# NinjaPCB_ver2_1.net
KiCad netlist of a schematic drawn in EAGLE
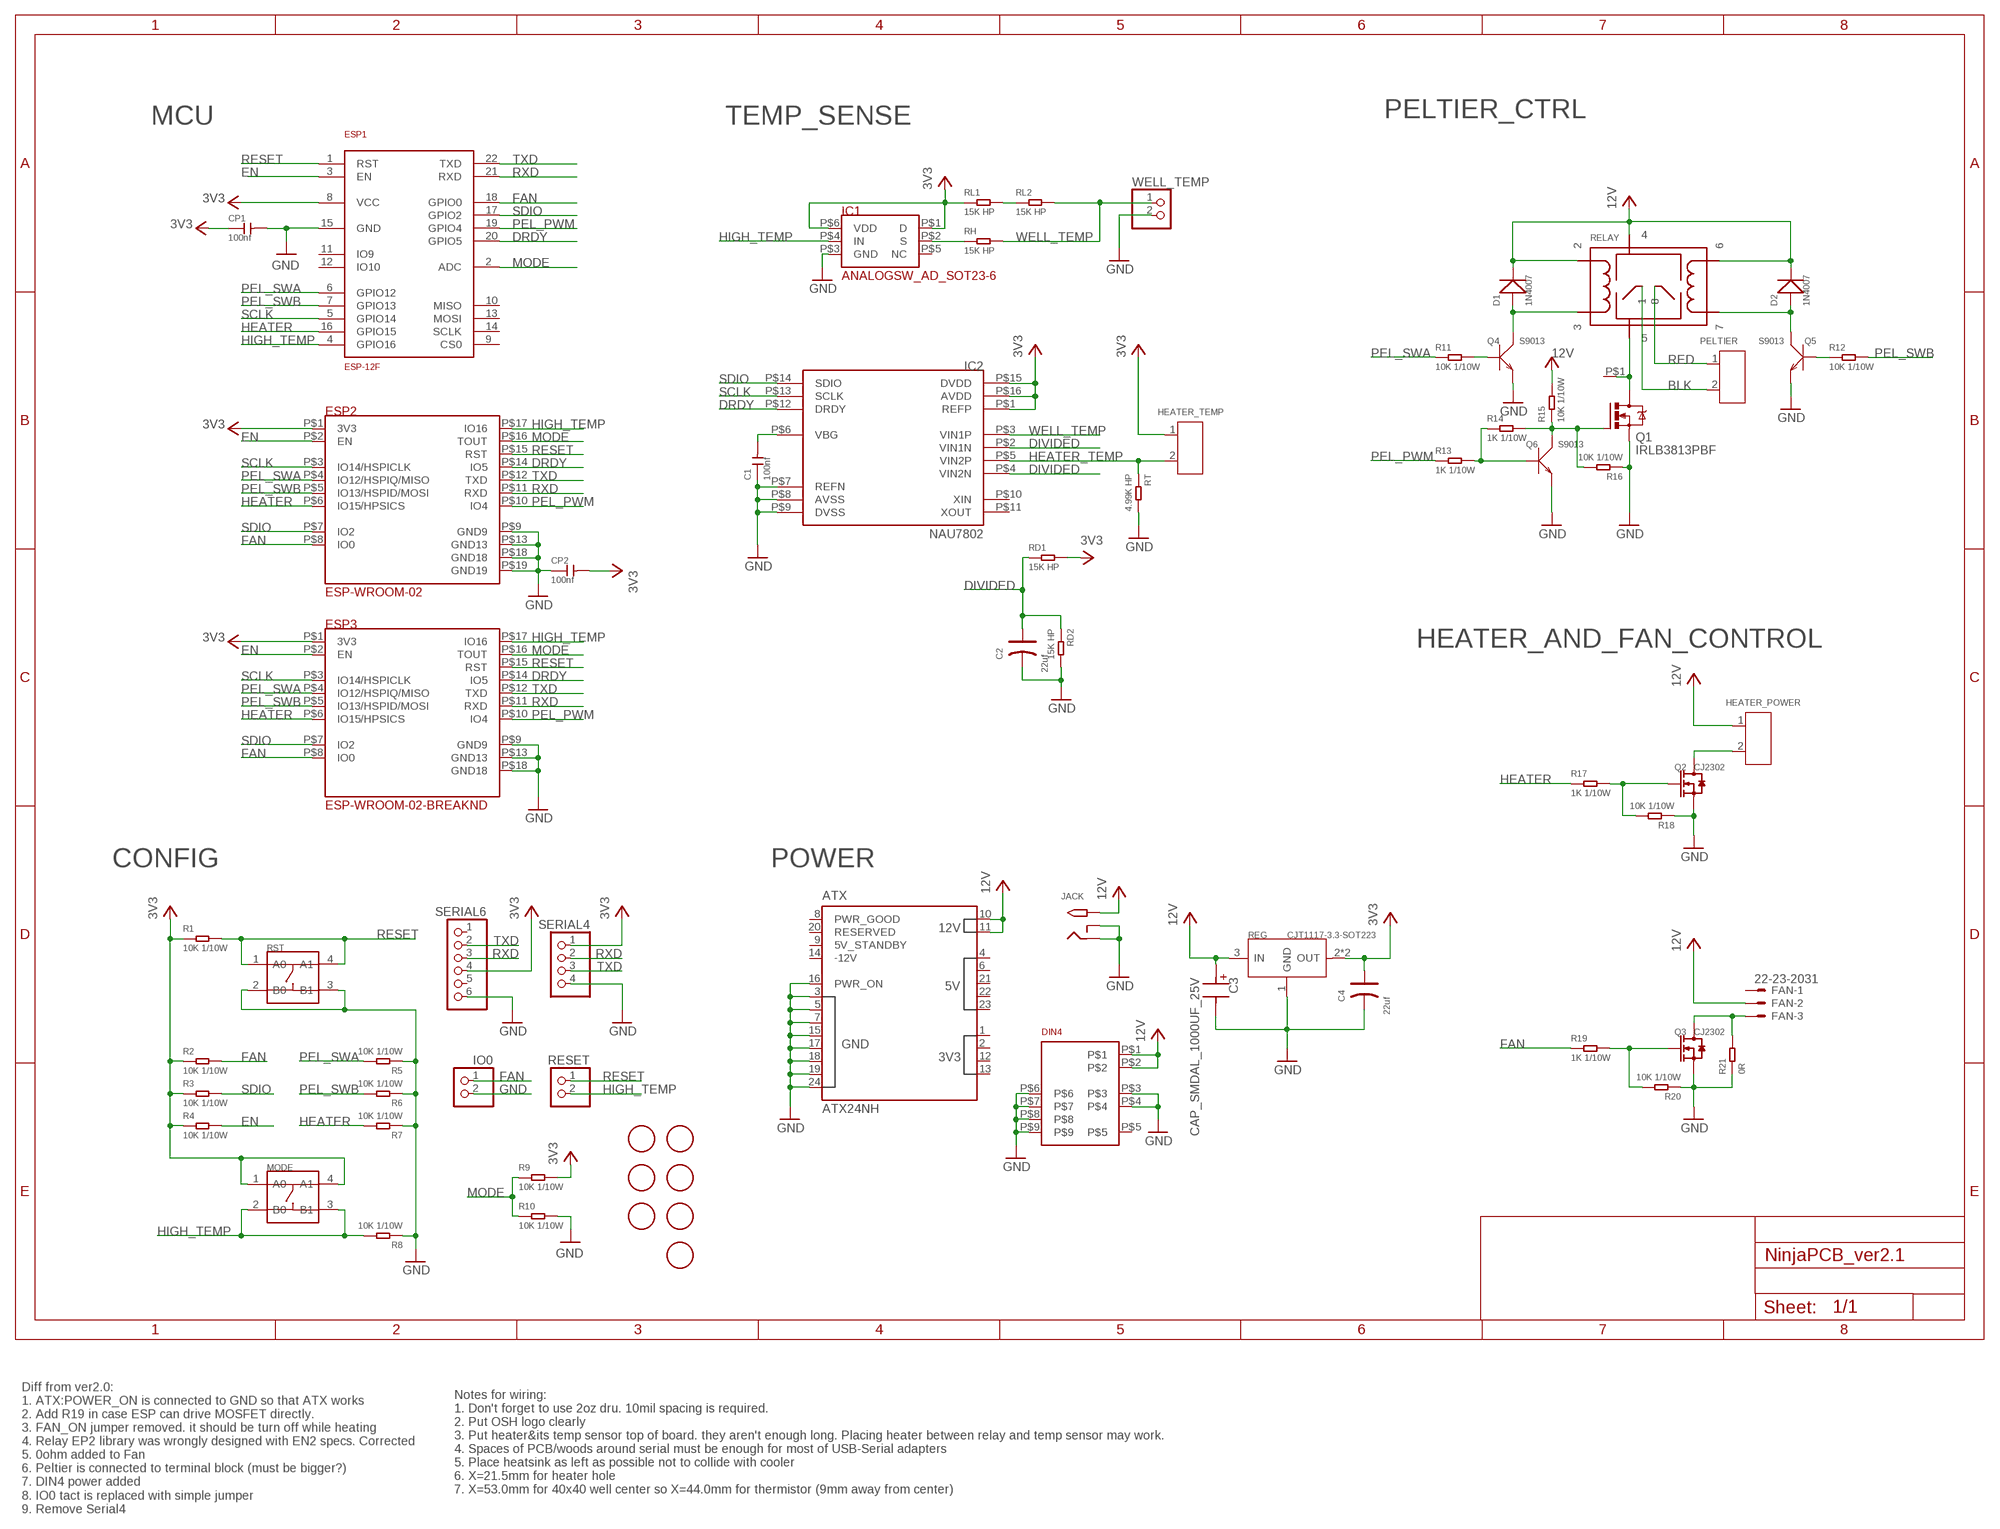
[diagram p0: schematic, sheet 1]

(export (version "E")
  (design (tool "Eeschema 10.0.6"))
  (components
    (comp (ref "ATX")
      (value "ATX24NH")
      (footprint "eagle-import:ATX24")
      (libsource (lib "eagle-import") (part "ATX24NH"))
    )
    (comp (ref "C1")
      (value "100nf")
      (footprint "eagle-import:C0603")
      (fields (field (name "MPN") "CC0603KRX7R9BB104"))
      (libsource (lib "eagle-import") (part "CERAMIC-100NF-50V-10%-X7R(0603)"))
    )
    (comp (ref "C2")
      (value "22uf")
      (footprint "eagle-import:AVX-B")
      (fields (field (name "MPN") "TAJB226*016#NJ"))
      (libsource (lib "eagle-import") (part "TANTALUM-SMD-22UF-16V(AVX-B)"))
    )
    (comp (ref "C3")
      (value "CAP_SMDAL_1000UF_25V")
      (footprint "eagle-import:CAP_SMD_AL_D125")
      (libsource (lib "eagle-import") (part "CAP_SMDAL_1000UF_25V"))
    )
    (comp (ref "C4")
      (value "22uf")
      (footprint "eagle-import:AVX-B")
      (fields (field (name "MPN") "TAJB226*016#NJ"))
      (libsource (lib "eagle-import") (part "TANTALUM-SMD-22UF-16V(AVX-B)"))
    )
    (comp (ref "CP1")
      (value "100nf")
      (footprint "eagle-import:C0603")
      (fields (field (name "MPN") "CC0603KRX7R9BB104"))
      (libsource (lib "eagle-import") (part "CERAMIC-100NF-50V-10%-X7R(0603)"))
    )
    (comp (ref "CP2")
      (value "100nf")
      (footprint "eagle-import:C0603")
      (fields (field (name "MPN") "CC0603KRX7R9BB104"))
      (libsource (lib "eagle-import") (part "CERAMIC-100NF-50V-10%-X7R(0603)"))
    )
    (comp (ref "D1")
      (value "1N4007")
      (footprint "eagle-import:DO-214AC")
      (libsource (lib "eagle-import") (part "DIODE-GEN-PURPOSE-1KV-1A(DO-214AC)"))
    )
    (comp (ref "D2")
      (value "1N4007")
      (footprint "eagle-import:DO-214AC")
      (libsource (lib "eagle-import") (part "DIODE-GEN-PURPOSE-1KV-1A(DO-214AC)"))
    )
    (comp (ref "DIN4")
      (value "DIN4")
      (footprint "eagle-import:DIN4")
      (libsource (lib "eagle-import") (part "DIN4"))
    )
    (comp (ref "ESP1")
      (value "ESP-12F")
      (footprint "eagle-import:ESP-12F")
      (libsource (lib "eagle-import") (part "ESP-12F"))
    )
    (comp (ref "ESP2")
      (value "ESP-WROOM-02")
      (footprint "eagle-import:ESP-WROOM-02")
      (libsource (lib "eagle-import") (part "ESP-WROOM-02"))
    )
    (comp (ref "ESP3")
      (value "ESP-WROOM-02-BREAKND")
      (footprint "eagle-import:ESP-WROOM-02-BREAK-NODETAIL")
      (libsource (lib "eagle-import") (part "ESP-WROOM-02-BREAKND"))
    )
    (comp (ref "FAN")
      (value "22-23-2031")
      (footprint "eagle-import:22-23-2031")
      (fields (field (name "MF") "MOLEX"))
      (libsource (lib "eagle-import") (part "22-23-2031"))
    )
    (comp (ref "HEATER_POWER")
      (value "SCREW-TERMINAL-GREEN(2P-3.5)")
      (footprint "eagle-import:H2-3.5-7.0X7.0MM")
      (libsource (lib "eagle-import") (part "SCREW-TERMINAL-GREEN(2P-3.5)"))
    )
    (comp (ref "HEATER_TEMP")
      (value "SCREW-TERMINAL-GREEN(2P-3.5)")
      (footprint "eagle-import:H2-3.5-7.0X7.0MM")
      (libsource (lib "eagle-import") (part "SCREW-TERMINAL-GREEN(2P-3.5)"))
    )
    (comp (ref "HEATSINK")
      (value "HEAT111PB015")
      (footprint "eagle-import:HEAT11PB015")
      (libsource (lib "eagle-import") (part "HEAT111PB015"))
    )
    (comp (ref "IC1")
      (value "ANALOGSW_AD_SOT23-6")
      (footprint "eagle-import:SOT-23-6")
      (libsource (lib "eagle-import") (part "ANALOGSW_AD_SOT23-6"))
    )
    (comp (ref "IC2")
      (value "NAU7802")
      (footprint "eagle-import:SOP-16")
      (libsource (lib "eagle-import") (part "NAU7802"))
    )
    (comp (ref "IO0")
      (value "PINHD-1X2")
      (footprint "eagle-import:1X02")
      (libsource (lib "eagle-import") (part "PINHD-1X2"))
    )
    (comp (ref "JACK")
      (value "2.1MMJACKTHM-NOOUT")
      (footprint "eagle-import:PJ-102A-NOOUT")
      (libsource (lib "eagle-import") (part "2.1MMJACKTHM-NOOUT"))
    )
    (comp (ref "MODE")
      (value "DIP-SWITCH-TACTILE-SPST-NO/TS-1109(4P-D6.0MM)'TS-1109'")
      (footprint "eagle-import:SW4-6.0X6.0X5.0MM")
      (libsource (lib "eagle-import") (part "DIP-SWITCH-TACTILE-SPST-NO/TS-1109(4P-D6.0MM)'TS-1109'"))
    )
    (comp (ref "PELTIER")
      (value "SCREW-TERMINAL-GREEN(2P-3.5)")
      (footprint "eagle-import:H2-3.5-7.0X7.0MM")
      (libsource (lib "eagle-import") (part "SCREW-TERMINAL-GREEN(2P-3.5)"))
    )
    (comp (ref "Q1")
      (value "IRLB3813PBF")
      (footprint "eagle-import:TO220BV")
      (libsource (lib "eagle-import") (part "IRF520"))
    )
    (comp (ref "Q2")
      (value "CJ2302")
      (footprint "eagle-import:SOT-23")
      (libsource (lib "eagle-import") (part "SMD-MOSFET-N-CH-20V-2.1A-CJ2302(SOT-23)"))
    )
    (comp (ref "Q3")
      (value "CJ2302")
      (footprint "eagle-import:SOT-23")
      (libsource (lib "eagle-import") (part "SMD-MOSFET-N-CH-20V-2.1A-CJ2302(SOT-23)"))
    )
    (comp (ref "Q4")
      (value "S9013")
      (footprint "eagle-import:SOT-23")
      (libsource (lib "eagle-import") (part "SMD-TRANSISTORS-NPN-25V-500MA-S9013(SOT-23)"))
    )
    (comp (ref "Q5")
      (value "S9013")
      (footprint "eagle-import:SOT-23")
      (libsource (lib "eagle-import") (part "SMD-TRANSISTORS-NPN-25V-500MA-S9013(SOT-23)"))
    )
    (comp (ref "Q6")
      (value "S9013")
      (footprint "eagle-import:SOT-23")
      (libsource (lib "eagle-import") (part "SMD-TRANSISTORS-NPN-25V-500MA-S9013(SOT-23)"))
    )
    (comp (ref "R1")
      (value "10K 1/10W")
      (footprint "eagle-import:R0603")
      (fields (field (name "MPN") "RC0603JR-0710KL"))
      (libsource (lib "eagle-import") (part "SMD-RES-10K-5%-1/10W(0603)"))
    )
    (comp (ref "R2")
      (value "10K 1/10W")
      (footprint "eagle-import:R0603")
      (fields (field (name "MPN") "RC0603JR-0710KL"))
      (libsource (lib "eagle-import") (part "SMD-RES-10K-5%-1/10W(0603)"))
    )
    (comp (ref "R3")
      (value "10K 1/10W")
      (footprint "eagle-import:R0603")
      (fields (field (name "MPN") "RC0603JR-0710KL"))
      (libsource (lib "eagle-import") (part "SMD-RES-10K-5%-1/10W(0603)"))
    )
    (comp (ref "R4")
      (value "10K 1/10W")
      (footprint "eagle-import:R0603")
      (fields (field (name "MPN") "RC0603JR-0710KL"))
      (libsource (lib "eagle-import") (part "SMD-RES-10K-5%-1/10W(0603)"))
    )
    (comp (ref "R5")
      (value "10K 1/10W")
      (footprint "eagle-import:R0603")
      (fields (field (name "MPN") "RC0603JR-0710KL"))
      (libsource (lib "eagle-import") (part "SMD-RES-10K-5%-1/10W(0603)"))
    )
    (comp (ref "R6")
      (value "10K 1/10W")
      (footprint "eagle-import:R0603")
      (fields (field (name "MPN") "RC0603JR-0710KL"))
      (libsource (lib "eagle-import") (part "SMD-RES-10K-5%-1/10W(0603)"))
    )
    (comp (ref "R7")
      (value "10K 1/10W")
      (footprint "eagle-import:R0603")
      (fields (field (name "MPN") "RC0603JR-0710KL"))
      (libsource (lib "eagle-import") (part "SMD-RES-10K-5%-1/10W(0603)"))
    )
    (comp (ref "R8")
      (value "10K 1/10W")
      (footprint "eagle-import:R0603")
      (fields (field (name "MPN") "RC0603JR-0710KL"))
      (libsource (lib "eagle-import") (part "SMD-RES-10K-5%-1/10W(0603)"))
    )
    (comp (ref "R9")
      (value "10K 1/10W")
      (footprint "eagle-import:R0603")
      (fields (field (name "MPN") "RC0603JR-0710KL"))
      (libsource (lib "eagle-import") (part "SMD-RES-10K-5%-1/10W(0603)"))
    )
    (comp (ref "R10")
      (value "10K 1/10W")
      (footprint "eagle-import:R0603")
      (fields (field (name "MPN") "RC0603JR-0710KL"))
      (libsource (lib "eagle-import") (part "SMD-RES-10K-5%-1/10W(0603)"))
    )
    (comp (ref "R11")
      (value "10K 1/10W")
      (footprint "eagle-import:R0603")
      (fields (field (name "MPN") "RC0603JR-0710KL"))
      (libsource (lib "eagle-import") (part "SMD-RES-10K-5%-1/10W(0603)"))
    )
    (comp (ref "R12")
      (value "10K 1/10W")
      (footprint "eagle-import:R0603")
      (fields (field (name "MPN") "RC0603JR-0710KL"))
      (libsource (lib "eagle-import") (part "SMD-RES-10K-5%-1/10W(0603)"))
    )
    (comp (ref "R13")
      (value "1K 1/10W")
      (footprint "eagle-import:R0603")
      (fields (field (name "MPN") "RC0603JR-071KL"))
      (libsource (lib "eagle-import") (part "SMD-RES-1K-5%-1/10W(0603)"))
    )
    (comp (ref "R14")
      (value "1K 1/10W")
      (footprint "eagle-import:R0603")
      (fields (field (name "MPN") "RC0603JR-071KL"))
      (libsource (lib "eagle-import") (part "SMD-RES-1K-5%-1/10W(0603)"))
    )
    (comp (ref "R15")
      (value "10K 1/10W")
      (footprint "eagle-import:R0603")
      (fields (field (name "MPN") "RC0603JR-0710KL"))
      (libsource (lib "eagle-import") (part "SMD-RES-10K-5%-1/10W(0603)"))
    )
    (comp (ref "R16")
      (value "10K 1/10W")
      (footprint "eagle-import:R0603")
      (fields (field (name "MPN") "RC0603JR-0710KL"))
      (libsource (lib "eagle-import") (part "SMD-RES-10K-5%-1/10W(0603)"))
    )
    (comp (ref "R17")
      (value "1K 1/10W")
      (footprint "eagle-import:R0603")
      (fields (field (name "MPN") "RC0603JR-071KL"))
      (libsource (lib "eagle-import") (part "SMD-RES-1K-5%-1/10W(0603)"))
    )
    (comp (ref "R18")
      (value "10K 1/10W")
      (footprint "eagle-import:R0603")
      (fields (field (name "MPN") "RC0603JR-0710KL"))
      (libsource (lib "eagle-import") (part "SMD-RES-10K-5%-1/10W(0603)"))
    )
    (comp (ref "R19")
      (value "1K 1/10W")
      (footprint "eagle-import:R0603")
      (fields (field (name "MPN") "RC0603JR-071KL"))
      (libsource (lib "eagle-import") (part "SMD-RES-1K-5%-1/10W(0603)"))
    )
    (comp (ref "R20")
      (value "10K 1/10W")
      (footprint "eagle-import:R0603")
      (fields (field (name "MPN") "RC0603JR-0710KL"))
      (libsource (lib "eagle-import") (part "SMD-RES-10K-5%-1/10W(0603)"))
    )
    (comp (ref "R21")
      (value "0R")
      (footprint "eagle-import:R0603")
      (fields (field (name "MPN") "RC0603JR-070RL"))
      (libsource (lib "eagle-import") (part "SMD-RES-0R-5%-1/10W(0603)"))
    )
    (comp (ref "RD1")
      (value "15K HP")
      (footprint "eagle-import:R0603")
      (libsource (lib "eagle-import") (part "R0603"))
    )
    (comp (ref "RD2")
      (value "15K HP")
      (footprint "eagle-import:R0603")
      (libsource (lib "eagle-import") (part "R0603"))
    )
    (comp (ref "REG")
      (value "CJT1117-3.3-SOT223")
      (footprint "eagle-import:SOT-223")
      (fields (field (name "MPN") "CJT1117-3.3"))
      (libsource (lib "eagle-import") (part "PMIC-CJT1117-3.3(SOT223)"))
    )
    (comp (ref "RELAY")
      (value "NEC-RELAY2EP2")
      (footprint "eagle-import:NEC-EP2")
      (libsource (lib "eagle-import") (part "NEC-RELAY2EP2"))
    )
    (comp (ref "RESET")
      (value "PINHD-1X2")
      (footprint "eagle-import:1X02")
      (libsource (lib "eagle-import") (part "PINHD-1X2"))
    )
    (comp (ref "RH")
      (value "15K HP")
      (footprint "eagle-import:R0603")
      (libsource (lib "eagle-import") (part "R0603"))
    )
    (comp (ref "RL1")
      (value "15K HP")
      (footprint "eagle-import:R0603")
      (libsource (lib "eagle-import") (part "R0603"))
    )
    (comp (ref "RL2")
      (value "15K HP")
      (footprint "eagle-import:R0603")
      (libsource (lib "eagle-import") (part "R0603"))
    )
    (comp (ref "RST")
      (value "DIP-SWITCH-TACTILE-SPST-NO/TS-1109(4P-D6.0MM)'TS-1109'")
      (footprint "eagle-import:SW4-6.0X6.0X5.0MM")
      (libsource (lib "eagle-import") (part "DIP-SWITCH-TACTILE-SPST-NO/TS-1109(4P-D6.0MM)'TS-1109'"))
    )
    (comp (ref "RT")
      (value "4.99K HP")
      (footprint "eagle-import:R0603")
      (fields (field (name "MPN") "RC0603FR-072KL"))
      (libsource (lib "eagle-import") (part "SMD-RES-2K-1%-1/10W(0603)"))
    )
    (comp (ref "SERIAL4")
      (value "PINHD-1X4")
      (footprint "eagle-import:1X04")
      (libsource (lib "eagle-import") (part "PINHD-1X4"))
    )
    (comp (ref "SERIAL6")
      (value "PINHD-1X6")
      (footprint "eagle-import:1X06")
      (libsource (lib "eagle-import") (part "PINHD-1X6"))
    )
    (comp (ref "U$3")
      (value "FIDUCIAL")
      (footprint "eagle-import:FIDUCIAL_1MM")
      (libsource (lib "eagle-import") (part "FIDUCIAL"))
    )
    (comp (ref "U$4")
      (value "FIDUCIAL")
      (footprint "eagle-import:FIDUCIAL_1MM")
      (libsource (lib "eagle-import") (part "FIDUCIAL"))
    )
    (comp (ref "U$5")
      (value "FIDUCIAL")
      (footprint "eagle-import:FIDUCIAL_1MM")
      (libsource (lib "eagle-import") (part "FIDUCIAL"))
    )
    (comp (ref "U$7")
      (value "FIDUCIAL")
      (footprint "eagle-import:FIDUCIAL_1MM")
      (libsource (lib "eagle-import") (part "FIDUCIAL"))
    )
    (comp (ref "U$8")
      (value "FIDUCIAL")
      (footprint "eagle-import:FIDUCIAL_1MM")
      (libsource (lib "eagle-import") (part "FIDUCIAL"))
    )
    (comp (ref "U$9")
      (value "FIDUCIAL")
      (footprint "eagle-import:FIDUCIAL_1MM")
      (libsource (lib "eagle-import") (part "FIDUCIAL"))
    )
    (comp (ref "U$10")
      (value "FIDUCIAL")
      (footprint "eagle-import:FIDUCIAL_1MM")
      (libsource (lib "eagle-import") (part "FIDUCIAL"))
    )
    (comp (ref "WELL_TEMP")
      (value "PINHD-1X2/90")
      (footprint "eagle-import:1X02_90")
      (libsource (lib "eagle-import") (part "PINHD-1X2/90"))
    )
  )
  (nets
    (net (code "1") (name "/BLK") (class "Default")
      (node (ref "PELTIER") (pin "2") (pinfunction "2_2") (pintype "bidirectional"))
      (node (ref "RELAY") (pin "P$1") (pinfunction "1_P$1") (pintype "bidirectional"))
    )
    (net (code "2") (name "/DIVIDED") (class "Default")
      (node (ref "C2") (pin "+") (pinfunction "+_+") (pintype "passive"))
      (node (ref "IC2") (pin "P$2") (pinfunction "VIN1N_P$2") (pintype "bidirectional"))
      (node (ref "IC2") (pin "P$4") (pinfunction "VIN2N_P$4") (pintype "bidirectional"))
      (node (ref "RD1") (pin "1") (pinfunction "1_1") (pintype "passive"))
      (node (ref "RD2") (pin "1") (pinfunction "1_1") (pintype "passive"))
    )
    (net (code "3") (name "/DRDY") (class "Default")
      (node (ref "ESP1") (pin "20") (pinfunction "GPIO5_20") (pintype "bidirectional"))
      (node (ref "ESP2") (pin "P$14") (pinfunction "IO5_P$14") (pintype "bidirectional"))
      (node (ref "ESP3") (pin "P$14") (pinfunction "IO5_P$14") (pintype "bidirectional"))
      (node (ref "IC2") (pin "P$12") (pinfunction "DRDY_P$12") (pintype "bidirectional"))
    )
    (net (code "4") (name "/EN") (class "Default")
      (node (ref "ESP1") (pin "3") (pinfunction "EN_3") (pintype "bidirectional"))
      (node (ref "ESP2") (pin "P$2") (pinfunction "EN_P$2") (pintype "bidirectional"))
      (node (ref "ESP3") (pin "P$2") (pinfunction "EN_P$2") (pintype "bidirectional"))
      (node (ref "R4") (pin "2") (pinfunction "2_2") (pintype "passive"))
    )
    (net (code "5") (name "/FAN") (class "Default")
      (node (ref "ESP1") (pin "18") (pinfunction "GPIO0_18") (pintype "bidirectional"))
      (node (ref "ESP2") (pin "P$8") (pinfunction "IO0_P$8") (pintype "bidirectional"))
      (node (ref "ESP3") (pin "P$8") (pinfunction "IO0_P$8") (pintype "bidirectional"))
      (node (ref "IO0") (pin "1") (pinfunction "1_1") (pintype "passive"))
      (node (ref "R19") (pin "1") (pinfunction "1_1") (pintype "passive"))
      (node (ref "R2") (pin "2") (pinfunction "2_2") (pintype "passive"))
    )
    (net (code "6") (name "/HEATER") (class "Default")
      (node (ref "ESP1") (pin "16") (pinfunction "GPIO15_16") (pintype "bidirectional"))
      (node (ref "ESP2") (pin "P$6") (pinfunction "IO15/HPSICS_P$6") (pintype "bidirectional"))
      (node (ref "ESP3") (pin "P$6") (pinfunction "IO15/HPSICS_P$6") (pintype "bidirectional"))
      (node (ref "R17") (pin "1") (pinfunction "1_1") (pintype "passive"))
      (node (ref "R7") (pin "2") (pinfunction "2_2") (pintype "passive"))
    )
    (net (code "7") (name "/HEATER_TEMP") (class "Default")
      (node (ref "HEATER_TEMP") (pin "2") (pinfunction "2_2") (pintype "bidirectional"))
      (node (ref "IC2") (pin "P$5") (pinfunction "VIN2P_P$5") (pintype "bidirectional"))
      (node (ref "RT") (pin "1") (pinfunction "1_1") (pintype "passive"))
    )
    (net (code "8") (name "/HIGH_TEMP") (class "Default")
      (node (ref "ESP1") (pin "4") (pinfunction "GPIO16_4") (pintype "bidirectional"))
      (node (ref "ESP2") (pin "P$17") (pinfunction "IO16_P$17") (pintype "bidirectional"))
      (node (ref "ESP3") (pin "P$17") (pinfunction "IO16_P$17") (pintype "bidirectional"))
      (node (ref "IC1") (pin "P$4") (pinfunction "IN_P$4") (pintype "bidirectional"))
      (node (ref "MODE") (pin "2") (pinfunction "B0_2") (pintype "bidirectional"))
      (node (ref "MODE") (pin "3") (pinfunction "B1_3") (pintype "bidirectional"))
      (node (ref "R8") (pin "2") (pinfunction "2_2") (pintype "passive"))
      (node (ref "RESET") (pin "2") (pinfunction "2_2") (pintype "passive"))
    )
    (net (code "9") (name "/MODE") (class "Default")
      (node (ref "ESP1") (pin "2") (pinfunction "ADC_2") (pintype "bidirectional"))
      (node (ref "ESP2") (pin "P$16") (pinfunction "TOUT_P$16") (pintype "bidirectional"))
      (node (ref "ESP3") (pin "P$16") (pinfunction "TOUT_P$16") (pintype "bidirectional"))
      (node (ref "R10") (pin "1") (pinfunction "1_1") (pintype "passive"))
      (node (ref "R9") (pin "1") (pinfunction "1_1") (pintype "passive"))
    )
    (net (code "10") (name "/PEL_PWM") (class "Default")
      (node (ref "ESP1") (pin "19") (pinfunction "GPIO4_19") (pintype "bidirectional"))
      (node (ref "ESP2") (pin "P$10") (pinfunction "IO4_P$10") (pintype "bidirectional"))
      (node (ref "ESP3") (pin "P$10") (pinfunction "IO4_P$10") (pintype "bidirectional"))
      (node (ref "R13") (pin "1") (pinfunction "1_1") (pintype "passive"))
    )
    (net (code "11") (name "/PEL_SWA") (class "Default")
      (node (ref "ESP1") (pin "6") (pinfunction "GPIO12_6") (pintype "bidirectional"))
      (node (ref "ESP2") (pin "P$4") (pinfunction "IO12/HSPIQ/MISO_P$4") (pintype "bidirectional"))
      (node (ref "ESP3") (pin "P$4") (pinfunction "IO12/HSPIQ/MISO_P$4") (pintype "bidirectional"))
      (node (ref "R11") (pin "1") (pinfunction "1_1") (pintype "passive"))
      (node (ref "R5") (pin "2") (pinfunction "2_2") (pintype "passive"))
    )
    (net (code "12") (name "/PEL_SWB") (class "Default")
      (node (ref "ESP1") (pin "7") (pinfunction "GPIO13_7") (pintype "bidirectional"))
      (node (ref "ESP2") (pin "P$5") (pinfunction "IO13/HSPID/MOSI_P$5") (pintype "bidirectional"))
      (node (ref "ESP3") (pin "P$5") (pinfunction "IO13/HSPID/MOSI_P$5") (pintype "bidirectional"))
      (node (ref "R12") (pin "2") (pinfunction "2_2") (pintype "passive"))
      (node (ref "R6") (pin "2") (pinfunction "2_2") (pintype "passive"))
    )
    (net (code "13") (name "/RED") (class "Default")
      (node (ref "PELTIER") (pin "1") (pinfunction "1_1") (pintype "bidirectional"))
      (node (ref "RELAY") (pin "P$8") (pinfunction "8_P$8") (pintype "bidirectional"))
    )
    (net (code "14") (name "/RESET") (class "Default")
      (node (ref "ESP1") (pin "1") (pinfunction "RST_1") (pintype "bidirectional"))
      (node (ref "ESP2") (pin "P$15") (pinfunction "RST_P$15") (pintype "bidirectional"))
      (node (ref "ESP3") (pin "P$15") (pinfunction "RST_P$15") (pintype "bidirectional"))
      (node (ref "R1") (pin "2") (pinfunction "2_2") (pintype "passive"))
      (node (ref "RESET") (pin "1") (pinfunction "1_1") (pintype "passive"))
      (node (ref "RST") (pin "1") (pinfunction "A0_1") (pintype "bidirectional"))
      (node (ref "RST") (pin "4") (pinfunction "A1_4") (pintype "bidirectional"))
    )
    (net (code "15") (name "/RXD") (class "Default")
      (node (ref "ESP1") (pin "21") (pinfunction "RXD_21") (pintype "bidirectional"))
      (node (ref "ESP2") (pin "P$11") (pinfunction "RXD_P$11") (pintype "bidirectional"))
      (node (ref "ESP3") (pin "P$11") (pinfunction "RXD_P$11") (pintype "bidirectional"))
      (node (ref "SERIAL4") (pin "2") (pinfunction "2_2") (pintype "passive"))
      (node (ref "SERIAL6") (pin "3") (pinfunction "3_3") (pintype "passive"))
    )
    (net (code "16") (name "/SCLK") (class "Default")
      (node (ref "ESP1") (pin "5") (pinfunction "GPIO14_5") (pintype "bidirectional"))
      (node (ref "ESP2") (pin "P$3") (pinfunction "IO14/HSPICLK_P$3") (pintype "bidirectional"))
      (node (ref "ESP3") (pin "P$3") (pinfunction "IO14/HSPICLK_P$3") (pintype "bidirectional"))
      (node (ref "IC2") (pin "P$13") (pinfunction "SCLK_P$13") (pintype "bidirectional"))
    )
    (net (code "17") (name "/SDIO") (class "Default")
      (node (ref "ESP1") (pin "17") (pinfunction "GPIO2_17") (pintype "bidirectional"))
      (node (ref "ESP2") (pin "P$7") (pinfunction "IO2_P$7") (pintype "bidirectional"))
      (node (ref "ESP3") (pin "P$7") (pinfunction "IO2_P$7") (pintype "bidirectional"))
      (node (ref "IC2") (pin "P$14") (pinfunction "SDIO_P$14") (pintype "bidirectional"))
      (node (ref "R3") (pin "2") (pinfunction "2_2") (pintype "passive"))
    )
    (net (code "18") (name "/TXD") (class "Default")
      (node (ref "ESP1") (pin "22") (pinfunction "TXD_22") (pintype "bidirectional"))
      (node (ref "ESP2") (pin "P$12") (pinfunction "TXD_P$12") (pintype "bidirectional"))
      (node (ref "ESP3") (pin "P$12") (pinfunction "TXD_P$12") (pintype "bidirectional"))
      (node (ref "SERIAL4") (pin "3") (pinfunction "3_3") (pintype "passive"))
      (node (ref "SERIAL6") (pin "2") (pinfunction "2_2") (pintype "passive"))
    )
    (net (code "19") (name "/WELL_TEMP") (class "Default")
      (node (ref "IC2") (pin "P$3") (pinfunction "VIN1P_P$3") (pintype "bidirectional"))
      (node (ref "RH") (pin "2") (pinfunction "2_2") (pintype "passive"))
      (node (ref "RL2") (pin "2") (pinfunction "2_2") (pintype "passive"))
      (node (ref "WELL_TEMP") (pin "1") (pinfunction "1_1") (pintype "passive"))
    )
    (net (code "20") (name "3V3") (class "Default")
      (node (ref "C4") (pin "+") (pinfunction "+_+") (pintype "passive"))
      (node (ref "CP1") (pin "1") (pinfunction "1_1") (pintype "passive"))
      (node (ref "CP2") (pin "2") (pinfunction "2_2") (pintype "passive"))
      (node (ref "ESP1") (pin "8") (pinfunction "VCC_8") (pintype "bidirectional"))
      (node (ref "ESP2") (pin "P$1") (pinfunction "3V3_P$1") (pintype "bidirectional"))
      (node (ref "ESP3") (pin "P$1") (pinfunction "3V3_P$1") (pintype "bidirectional"))
      (node (ref "HEATER_TEMP") (pin "1") (pinfunction "1_1") (pintype "bidirectional"))
      (node (ref "IC1") (pin "P$1") (pinfunction "D_P$1") (pintype "bidirectional"))
      (node (ref "IC1") (pin "P$6") (pinfunction "VDD_P$6") (pintype "bidirectional"))
      (node (ref "IC2") (pin "P$1") (pinfunction "REFP_P$1") (pintype "bidirectional"))
      (node (ref "IC2") (pin "P$15") (pinfunction "DVDD_P$15") (pintype "bidirectional"))
      (node (ref "IC2") (pin "P$16") (pinfunction "AVDD_P$16") (pintype "bidirectional"))
      (node (ref "MODE") (pin "1") (pinfunction "A0_1") (pintype "bidirectional"))
      (node (ref "MODE") (pin "4") (pinfunction "A1_4") (pintype "bidirectional"))
      (node (ref "R1") (pin "1") (pinfunction "1_1") (pintype "passive"))
      (node (ref "R2") (pin "1") (pinfunction "1_1") (pintype "passive"))
      (node (ref "R3") (pin "1") (pinfunction "1_1") (pintype "passive"))
      (node (ref "R4") (pin "1") (pinfunction "1_1") (pintype "passive"))
      (node (ref "R9") (pin "2") (pinfunction "2_2") (pintype "passive"))
      (node (ref "RD1") (pin "2") (pinfunction "2_2") (pintype "passive"))
      (node (ref "REG") (pin "2") (pinfunction "OUT_2") (pintype "bidirectional"))
      (node (ref "REG") (pin "TER") (pinfunction "OUT_TER") (pintype "bidirectional"))
      (node (ref "RL1") (pin "1") (pinfunction "1_1") (pintype "passive"))
      (node (ref "SERIAL4") (pin "1") (pinfunction "1_1") (pintype "passive"))
      (node (ref "SERIAL6") (pin "4") (pinfunction "4_4") (pintype "passive"))
    )
    (net (code "21") (name "12V") (class "Default")
      (node (ref "ATX") (pin "10") (pinfunction "12V_10_10") (pintype "bidirectional"))
      (node (ref "ATX") (pin "11") (pinfunction "12V_11_11") (pintype "bidirectional"))
      (node (ref "C3") (pin "P$P") (pinfunction "P$P_P$P") (pintype "passive"))
      (node (ref "D1") (pin "2") (pinfunction "-_2") (pintype "passive"))
      (node (ref "D2") (pin "2") (pinfunction "-_2") (pintype "passive"))
      (node (ref "DIN4") (pin "P$1") (pinfunction "P$1_P$1") (pintype "bidirectional"))
      (node (ref "DIN4") (pin "P$2") (pinfunction "P$2_P$2") (pintype "bidirectional"))
      (node (ref "FAN") (pin "2") (pinfunction "S_2") (pintype "passive"))
      (node (ref "HEATER_POWER") (pin "1") (pinfunction "1_1") (pintype "bidirectional"))
      (node (ref "JACK") (pin "TIP") (pinfunction "TIP_TIP") (pintype "bidirectional"))
      (node (ref "R15") (pin "2") (pinfunction "2_2") (pintype "passive"))
      (node (ref "REG") (pin "3") (pinfunction "IN_3") (pintype "bidirectional"))
      (node (ref "RELAY") (pin "P$2") (pinfunction "2_P$2") (pintype "bidirectional"))
      (node (ref "RELAY") (pin "P$4") (pinfunction "4_P$4") (pintype "bidirectional"))
      (node (ref "RELAY") (pin "P$6") (pinfunction "6_P$6") (pintype "bidirectional"))
    )
    (net (code "22") (name "GND") (class "Default")
      (node (ref "ATX") (pin "15") (pinfunction "GND15_15") (pintype "bidirectional"))
      (node (ref "ATX") (pin "16") (pinfunction "PWR_ON_16") (pintype "bidirectional"))
      (node (ref "ATX") (pin "17") (pinfunction "GND17_17") (pintype "bidirectional"))
      (node (ref "ATX") (pin "18") (pinfunction "GND18_18") (pintype "bidirectional"))
      (node (ref "ATX") (pin "19") (pinfunction "GND19_19") (pintype "bidirectional"))
      (node (ref "ATX") (pin "24") (pinfunction "GND24_24") (pintype "bidirectional"))
      (node (ref "ATX") (pin "3") (pinfunction "GND3_3") (pintype "bidirectional"))
      (node (ref "ATX") (pin "5") (pinfunction "GND5_5") (pintype "bidirectional"))
      (node (ref "ATX") (pin "7") (pinfunction "GND7_7") (pintype "bidirectional"))
      (node (ref "C1") (pin "1") (pinfunction "1_1") (pintype "passive"))
      (node (ref "C2") (pin "-") (pinfunction "-_-") (pintype "passive"))
      (node (ref "C3") (pin "P$M") (pinfunction "P$M_P$M") (pintype "passive"))
      (node (ref "C4") (pin "-") (pinfunction "-_-") (pintype "passive"))
      (node (ref "CP1") (pin "2") (pinfunction "2_2") (pintype "passive"))
      (node (ref "CP2") (pin "1") (pinfunction "1_1") (pintype "passive"))
      (node (ref "DIN4") (pin "P$3") (pinfunction "P$3_P$3") (pintype "bidirectional"))
      (node (ref "DIN4") (pin "P$4") (pinfunction "P$4_P$4") (pintype "bidirectional"))
      (node (ref "DIN4") (pin "P$6") (pinfunction "P$6_P$6") (pintype "bidirectional"))
      (node (ref "DIN4") (pin "P$7") (pinfunction "P$7_P$7") (pintype "bidirectional"))
      (node (ref "DIN4") (pin "P$8") (pinfunction "P$8_P$8") (pintype "bidirectional"))
      (node (ref "DIN4") (pin "P$9") (pinfunction "P$9_P$9") (pintype "bidirectional"))
      (node (ref "ESP1") (pin "15") (pinfunction "GND_15") (pintype "bidirectional"))
      (node (ref "ESP2") (pin "P$13") (pinfunction "GND13_P$13") (pintype "bidirectional"))
      (node (ref "ESP2") (pin "P$18") (pinfunction "GND18_P$18") (pintype "bidirectional"))
      (node (ref "ESP2") (pin "P$19") (pinfunction "GND19_P$19") (pintype "bidirectional"))
      (node (ref "ESP2") (pin "P$9") (pinfunction "GND9_P$9") (pintype "bidirectional"))
      (node (ref "ESP3") (pin "P$13") (pinfunction "GND13_P$13") (pintype "bidirectional"))
      (node (ref "ESP3") (pin "P$18") (pinfunction "GND18_P$18") (pintype "bidirectional"))
      (node (ref "ESP3") (pin "P$9") (pinfunction "GND9_P$9") (pintype "bidirectional"))
      (node (ref "IC1") (pin "P$3") (pinfunction "GND_P$3") (pintype "bidirectional"))
      (node (ref "IC2") (pin "P$7") (pinfunction "REFN_P$7") (pintype "bidirectional"))
      (node (ref "IC2") (pin "P$8") (pinfunction "AVSS_P$8") (pintype "bidirectional"))
      (node (ref "IC2") (pin "P$9") (pinfunction "DVSS_P$9") (pintype "bidirectional"))
      (node (ref "IO0") (pin "2") (pinfunction "2_2") (pintype "passive"))
      (node (ref "JACK") (pin "RING") (pinfunction "RING_RING") (pintype "bidirectional"))
      (node (ref "JACK") (pin "RING_SW") (pinfunction "RING_SW_RING_SW") (pintype "bidirectional"))
      (node (ref "Q1") (pin "S") (pinfunction "S_S") (pintype "passive"))
      (node (ref "Q2") (pin "2") (pinfunction "S_2") (pintype "passive"))
      (node (ref "Q3") (pin "2") (pinfunction "S_2") (pintype "passive"))
      (node (ref "Q4") (pin "2") (pinfunction "E_2") (pintype "passive"))
      (node (ref "Q5") (pin "2") (pinfunction "E_2") (pintype "passive"))
      (node (ref "Q6") (pin "2") (pinfunction "E_2") (pintype "passive"))
      (node (ref "R10") (pin "2") (pinfunction "2_2") (pintype "passive"))
      (node (ref "R16") (pin "1") (pinfunction "1_1") (pintype "passive"))
      (node (ref "R18") (pin "1") (pinfunction "1_1") (pintype "passive"))
      (node (ref "R20") (pin "1") (pinfunction "1_1") (pintype "passive"))
      (node (ref "R21") (pin "1") (pinfunction "1_1") (pintype "passive"))
      (node (ref "R5") (pin "1") (pinfunction "1_1") (pintype "passive"))
      (node (ref "R6") (pin "1") (pinfunction "1_1") (pintype "passive"))
      (node (ref "R7") (pin "1") (pinfunction "1_1") (pintype "passive"))
      (node (ref "R8") (pin "1") (pinfunction "1_1") (pintype "passive"))
      (node (ref "RD2") (pin "2") (pinfunction "2_2") (pintype "passive"))
      (node (ref "REG") (pin "1") (pinfunction "GND_1") (pintype "bidirectional"))
      (node (ref "RST") (pin "2") (pinfunction "B0_2") (pintype "bidirectional"))
      (node (ref "RST") (pin "3") (pinfunction "B1_3") (pintype "bidirectional"))
      (node (ref "RT") (pin "2") (pinfunction "2_2") (pintype "passive"))
      (node (ref "SERIAL4") (pin "4") (pinfunction "4_4") (pintype "passive"))
      (node (ref "SERIAL6") (pin "6") (pinfunction "6_6") (pintype "passive"))
      (node (ref "WELL_TEMP") (pin "2") (pinfunction "2_2") (pintype "passive"))
    )
    (net (code "23") (name "Net-(D1-+)") (class "Default")
      (node (ref "D1") (pin "1") (pinfunction "+_1") (pintype "passive"))
      (node (ref "Q4") (pin "3") (pinfunction "C_3") (pintype "passive"))
      (node (ref "RELAY") (pin "P$3") (pinfunction "3_P$3") (pintype "bidirectional"))
    )
    (net (code "24") (name "Net-(D2-+)") (class "Default")
      (node (ref "D2") (pin "1") (pinfunction "+_1") (pintype "passive"))
      (node (ref "Q5") (pin "3") (pinfunction "C_3") (pintype "passive"))
      (node (ref "RELAY") (pin "P$7") (pinfunction "7_P$7") (pintype "bidirectional"))
    )
    (net (code "25") (name "Net-(FANC-S)") (class "Default")
      (node (ref "FAN") (pin "3") (pinfunction "S_3") (pintype "passive"))
      (node (ref "Q3") (pin "3") (pinfunction "D_3") (pintype "passive"))
      (node (ref "R21") (pin "2") (pinfunction "2_2") (pintype "passive"))
    )
    (net (code "26") (name "Net-(IC1-S)") (class "Default")
      (node (ref "IC1") (pin "P$2") (pinfunction "S_P$2") (pintype "bidirectional"))
      (node (ref "RH") (pin "1") (pinfunction "1_1") (pintype "passive"))
    )
    (net (code "27") (name "Net-(IC2-VBG)") (class "Default")
      (node (ref "C1") (pin "2") (pinfunction "2_2") (pintype "passive"))
      (node (ref "IC2") (pin "P$6") (pinfunction "VBG_P$6") (pintype "bidirectional"))
    )
    (net (code "28") (name "Net-(Q2-D)") (class "Default")
      (node (ref "HEATER_POWER") (pin "2") (pinfunction "2_2") (pintype "bidirectional"))
      (node (ref "Q2") (pin "3") (pinfunction "D_3") (pintype "passive"))
    )
    (net (code "29") (name "Net-(Q2-G)") (class "Default")
      (node (ref "Q2") (pin "1") (pinfunction "G_1") (pintype "passive"))
      (node (ref "R17") (pin "2") (pinfunction "2_2") (pintype "passive"))
      (node (ref "R18") (pin "2") (pinfunction "2_2") (pintype "passive"))
    )
    (net (code "30") (name "Net-(Q3-G)") (class "Default")
      (node (ref "Q3") (pin "1") (pinfunction "G_1") (pintype "passive"))
      (node (ref "R19") (pin "2") (pinfunction "2_2") (pintype "passive"))
      (node (ref "R20") (pin "2") (pinfunction "2_2") (pintype "passive"))
    )
    (net (code "31") (name "Net-(Q4-B)") (class "Default")
      (node (ref "Q4") (pin "1") (pinfunction "B_1") (pintype "passive"))
      (node (ref "R11") (pin "2") (pinfunction "2_2") (pintype "passive"))
    )
    (net (code "32") (name "Net-(Q5-B)") (class "Default")
      (node (ref "Q5") (pin "1") (pinfunction "B_1") (pintype "passive"))
      (node (ref "R12") (pin "1") (pinfunction "1_1") (pintype "passive"))
    )
    (net (code "33") (name "Net-(Q6-B)") (class "Default")
      (node (ref "Q6") (pin "1") (pinfunction "B_1") (pintype "passive"))
      (node (ref "R13") (pin "2") (pinfunction "2_2") (pintype "passive"))
      (node (ref "R14") (pin "1") (pinfunction "1_1") (pintype "passive"))
    )
    (net (code "34") (name "Net-(Q6-C)") (class "Default")
      (node (ref "Q1") (pin "G") (pinfunction "G_G") (pintype "passive"))
      (node (ref "Q6") (pin "3") (pinfunction "C_3") (pintype "passive"))
      (node (ref "R14") (pin "2") (pinfunction "2_2") (pintype "passive"))
      (node (ref "R15") (pin "1") (pinfunction "1_1") (pintype "passive"))
      (node (ref "R16") (pin "2") (pinfunction "2_2") (pintype "passive"))
    )
    (net (code "35") (name "Net-(RELAY-5)") (class "Default")
      (node (ref "HEATSINK") (pin "P$1") (pinfunction "P$1_P$1") (pintype "bidirectional"))
      (node (ref "Q1") (pin "D") (pinfunction "D_D") (pintype "passive"))
      (node (ref "RELAY") (pin "P$5") (pinfunction "5_P$5") (pintype "bidirectional"))
    )
    (net (code "36") (name "Net-(RL1-Pad2)") (class "Default")
      (node (ref "RL1") (pin "2") (pinfunction "2_2") (pintype "passive"))
      (node (ref "RL2") (pin "1") (pinfunction "1_1") (pintype "passive"))
    )
    (net (code "37") (name "unconnected-(ATX--12V-Pad14)") (class "Default")
      (node (ref "ATX") (pin "14") (pinfunction "-12V_14") (pintype "bidirectional"))
    )
    (net (code "38") (name "unconnected-(ATX-3V3_1-Pad1)") (class "Default")
      (node (ref "ATX") (pin "1") (pinfunction "3V3_1_1") (pintype "bidirectional"))
    )
    (net (code "39") (name "unconnected-(ATX-3V3_2-Pad2)") (class "Default")
      (node (ref "ATX") (pin "2") (pinfunction "3V3_2_2") (pintype "bidirectional"))
    )
    (net (code "40") (name "unconnected-(ATX-3V3_12-Pad12)") (class "Default")
      (node (ref "ATX") (pin "12") (pinfunction "3V3_12_12") (pintype "bidirectional"))
    )
    (net (code "41") (name "unconnected-(ATX-3V3_13-Pad13)") (class "Default")
      (node (ref "ATX") (pin "13") (pinfunction "3V3_13_13") (pintype "bidirectional"))
    )
    (net (code "42") (name "unconnected-(ATX-5V_4-Pad4)") (class "Default")
      (node (ref "ATX") (pin "4") (pinfunction "5V_4_4") (pintype "bidirectional"))
    )
    (net (code "43") (name "unconnected-(ATX-5V_6-Pad6)") (class "Default")
      (node (ref "ATX") (pin "6") (pinfunction "5V_6_6") (pintype "bidirectional"))
    )
    (net (code "44") (name "unconnected-(ATX-5V_21-Pad21)") (class "Default")
      (node (ref "ATX") (pin "21") (pinfunction "5V_21_21") (pintype "bidirectional"))
    )
    (net (code "45") (name "unconnected-(ATX-5V_22-Pad22)") (class "Default")
      (node (ref "ATX") (pin "22") (pinfunction "5V_22_22") (pintype "bidirectional"))
    )
    (net (code "46") (name "unconnected-(ATX-5V_23-Pad23)") (class "Default")
      (node (ref "ATX") (pin "23") (pinfunction "5V_23_23") (pintype "bidirectional"))
    )
    (net (code "47") (name "unconnected-(ATX-5V_STANDBY-Pad9)") (class "Default")
      (node (ref "ATX") (pin "9") (pinfunction "5V_STANDBY_9") (pintype "bidirectional"))
    )
    (net (code "48") (name "unconnected-(ATX-PWR_GOOD-Pad8)") (class "Default")
      (node (ref "ATX") (pin "8") (pinfunction "PWR_GOOD_8") (pintype "bidirectional"))
    )
    (net (code "49") (name "unconnected-(ATX-RESERVED-Pad20)") (class "Default")
      (node (ref "ATX") (pin "20") (pinfunction "RESERVED_20") (pintype "bidirectional"))
    )
    (net (code "50") (name "unconnected-(DIN4-PadP$5)") (class "Default")
      (node (ref "DIN4") (pin "P$5") (pinfunction "P$5_P$5") (pintype "bidirectional"))
    )
    (net (code "51") (name "unconnected-(ESP1-CS0-Pad9)") (class "Default")
      (node (ref "ESP1") (pin "9") (pinfunction "CS0_9") (pintype "bidirectional"))
    )
    (net (code "52") (name "unconnected-(ESP1-IO9-Pad11)") (class "Default")
      (node (ref "ESP1") (pin "11") (pinfunction "IO9_11") (pintype "bidirectional"))
    )
    (net (code "53") (name "unconnected-(ESP1-IO10-Pad12)") (class "Default")
      (node (ref "ESP1") (pin "12") (pinfunction "IO10_12") (pintype "bidirectional"))
    )
    (net (code "54") (name "unconnected-(ESP1-MISO-Pad10)") (class "Default")
      (node (ref "ESP1") (pin "10") (pinfunction "MISO_10") (pintype "bidirectional"))
    )
    (net (code "55") (name "unconnected-(ESP1-MOSI-Pad13)") (class "Default")
      (node (ref "ESP1") (pin "13") (pinfunction "MOSI_13") (pintype "bidirectional"))
    )
    (net (code "56") (name "unconnected-(ESP1-SCLK-Pad14)") (class "Default")
      (node (ref "ESP1") (pin "14") (pinfunction "SCLK_14") (pintype "bidirectional"))
    )
    (net (code "57") (name "unconnected-(FANA-S-Pad1)") (class "Default")
      (node (ref "FAN") (pin "1") (pinfunction "S_1") (pintype "passive"))
    )
    (net (code "58") (name "unconnected-(IC1-NC-PadP$5)") (class "Default")
      (node (ref "IC1") (pin "P$5") (pinfunction "NC_P$5") (pintype "bidirectional"))
    )
    (net (code "59") (name "unconnected-(IC2-XIN-PadP$10)") (class "Default")
      (node (ref "IC2") (pin "P$10") (pinfunction "XIN_P$10") (pintype "bidirectional"))
    )
    (net (code "60") (name "unconnected-(IC2-XOUT-PadP$11)") (class "Default")
      (node (ref "IC2") (pin "P$11") (pinfunction "XOUT_P$11") (pintype "bidirectional"))
    )
    (net (code "61") (name "unconnected-(SERIAL6-Pad1)") (class "Default")
      (node (ref "SERIAL6") (pin "1") (pinfunction "1_1") (pintype "passive"))
    )
    (net (code "62") (name "unconnected-(SERIAL6-Pad5)") (class "Default")
      (node (ref "SERIAL6") (pin "5") (pinfunction "5_5") (pintype "passive"))
    )
  )
)
